# ICAN-7006-MIC.net
KiCad netlist of a schematic drawn in Altium Designer
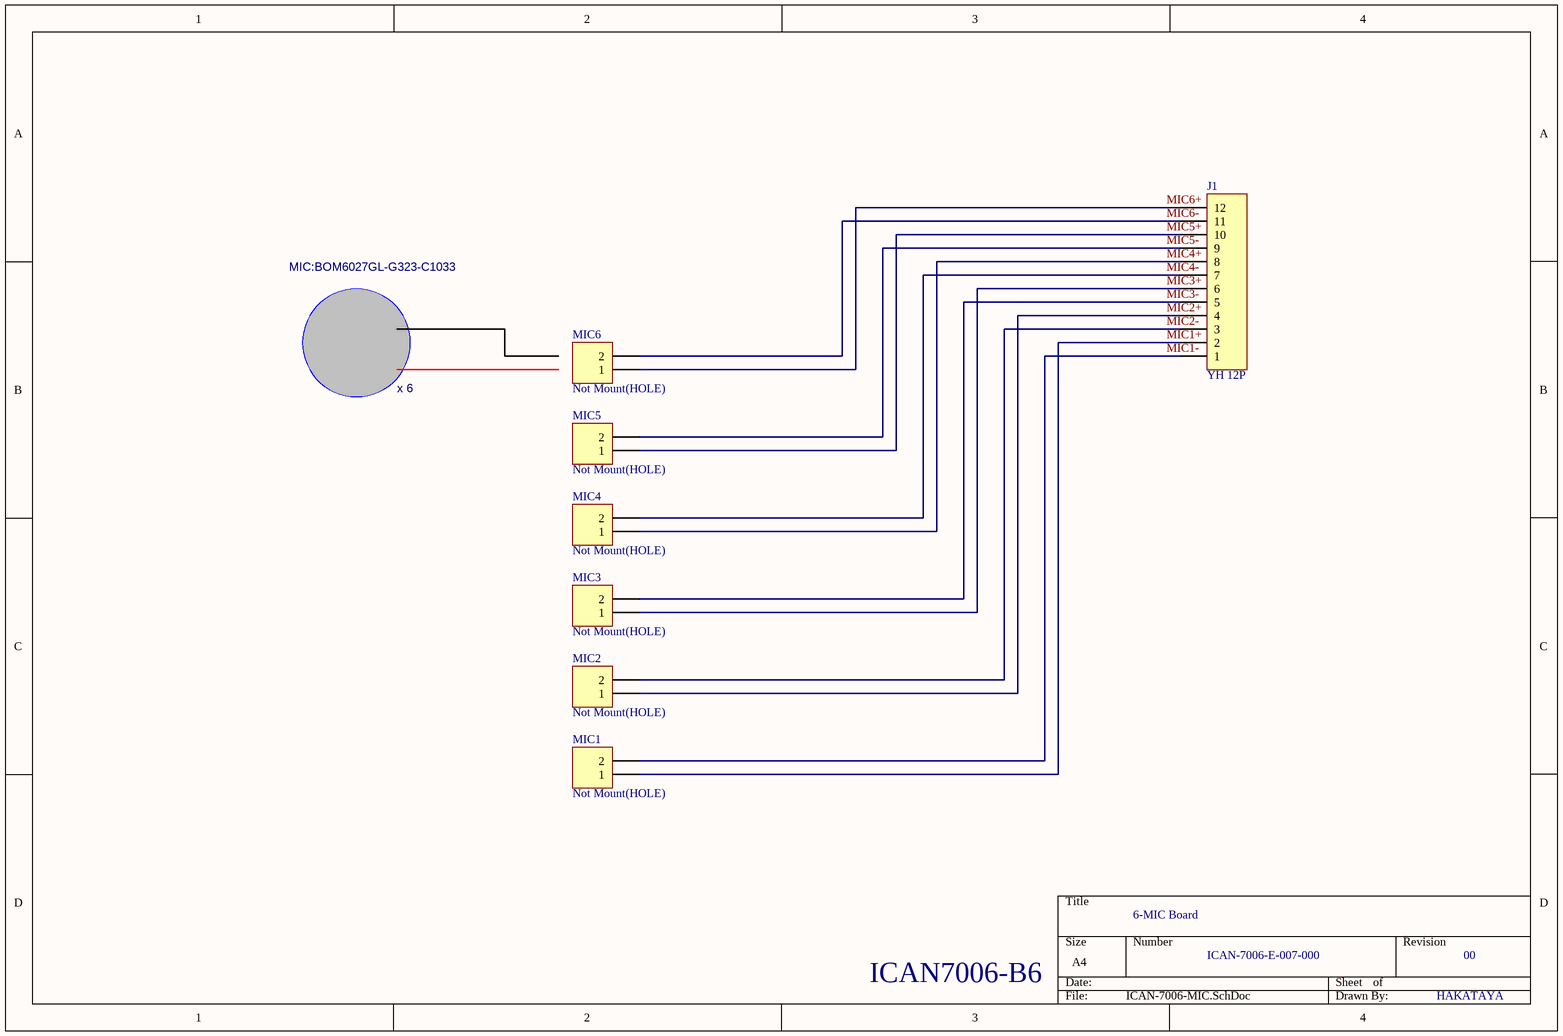
[diagram p0: ICAN-7006-MIC.SchDoc]

(export (version "E")
  (design (tool "Eeschema 10.0.6"))
  (components
    (comp (ref "J1")
      (value "YH 12P")
      (footprint "Miscellaneous Connectors:HDR2X6")
      (description "Header, 12-Pin")
      (fields (field (name "PUBLISHER") "Altium Limited"))
      (libsource (lib "Miscellaneous Connectors") (part "Header 12"))
    )
    (comp (ref "MIC1")
      (value "Not Mount(HOLE)")
      (footprint "Miscellaneous Connectors:MHDR1X2")
      (description "Header, 2-Pin")
      (fields (field (name "PUBLISHER") "Altium Limited"))
      (libsource (lib "Miscellaneous Connectors") (part "Header 2"))
    )
    (comp (ref "MIC2")
      (value "Not Mount(HOLE)")
      (footprint "Miscellaneous Connectors:MHDR1X2")
      (description "Header, 2-Pin")
      (fields (field (name "PUBLISHER") "Altium Limited"))
      (libsource (lib "Miscellaneous Connectors") (part "Header 2"))
    )
    (comp (ref "MIC3")
      (value "Not Mount(HOLE)")
      (footprint "Miscellaneous Connectors:MHDR1X2")
      (description "Header, 2-Pin")
      (fields (field (name "PUBLISHER") "Altium Limited"))
      (libsource (lib "Miscellaneous Connectors") (part "Header 2"))
    )
    (comp (ref "MIC4")
      (value "Not Mount(HOLE)")
      (footprint "Miscellaneous Connectors:MHDR1X2")
      (description "Header, 2-Pin")
      (fields (field (name "PUBLISHER") "Altium Limited"))
      (libsource (lib "Miscellaneous Connectors") (part "Header 2"))
    )
    (comp (ref "MIC5")
      (value "Not Mount(HOLE)")
      (footprint "Miscellaneous Connectors:MHDR1X2")
      (description "Header, 2-Pin")
      (fields (field (name "PUBLISHER") "Altium Limited"))
      (libsource (lib "Miscellaneous Connectors") (part "Header 2"))
    )
    (comp (ref "MIC6")
      (value "Not Mount(HOLE)")
      (footprint "Miscellaneous Connectors:MHDR1X2")
      (description "Header, 2-Pin")
      (fields (field (name "PUBLISHER") "Altium Limited"))
      (libsource (lib "Miscellaneous Connectors") (part "Header 2"))
    )
  )
  (nets
    (net (code "1") (name "/MIC1+") (class "Default")
      (node (ref "J1") (pin "2") (pinfunction "2_2") (pintype "passive"))
      (node (ref "MIC1") (pin "1") (pinfunction "1_1") (pintype "passive"))
    )
    (net (code "2") (name "/MIC1-") (class "Default")
      (node (ref "J1") (pin "1") (pinfunction "1_1") (pintype "passive"))
      (node (ref "MIC1") (pin "2") (pinfunction "2_2") (pintype "passive"))
    )
    (net (code "3") (name "/MIC2+") (class "Default")
      (node (ref "J1") (pin "4") (pinfunction "4_4") (pintype "passive"))
      (node (ref "MIC2") (pin "1") (pinfunction "1_1") (pintype "passive"))
    )
    (net (code "4") (name "/MIC2-") (class "Default")
      (node (ref "J1") (pin "3") (pinfunction "3_3") (pintype "passive"))
      (node (ref "MIC2") (pin "2") (pinfunction "2_2") (pintype "passive"))
    )
    (net (code "5") (name "/MIC3+") (class "Default")
      (node (ref "J1") (pin "6") (pinfunction "6_6") (pintype "passive"))
      (node (ref "MIC3") (pin "1") (pinfunction "1_1") (pintype "passive"))
    )
    (net (code "6") (name "/MIC3-") (class "Default")
      (node (ref "J1") (pin "5") (pinfunction "5_5") (pintype "passive"))
      (node (ref "MIC3") (pin "2") (pinfunction "2_2") (pintype "passive"))
    )
    (net (code "7") (name "/MIC4+") (class "Default")
      (node (ref "J1") (pin "8") (pinfunction "8_8") (pintype "passive"))
      (node (ref "MIC4") (pin "1") (pinfunction "1_1") (pintype "passive"))
    )
    (net (code "8") (name "/MIC4-") (class "Default")
      (node (ref "J1") (pin "7") (pinfunction "7_7") (pintype "passive"))
      (node (ref "MIC4") (pin "2") (pinfunction "2_2") (pintype "passive"))
    )
    (net (code "9") (name "/MIC5+") (class "Default")
      (node (ref "J1") (pin "10") (pinfunction "10_10") (pintype "passive"))
      (node (ref "MIC5") (pin "1") (pinfunction "1_1") (pintype "passive"))
    )
    (net (code "10") (name "/MIC5-") (class "Default")
      (node (ref "J1") (pin "9") (pinfunction "9_9") (pintype "passive"))
      (node (ref "MIC5") (pin "2") (pinfunction "2_2") (pintype "passive"))
    )
    (net (code "11") (name "/MIC6+") (class "Default")
      (node (ref "J1") (pin "12") (pinfunction "12_12") (pintype "passive"))
      (node (ref "MIC6") (pin "1") (pinfunction "1_1") (pintype "passive"))
    )
    (net (code "12") (name "/MIC6-") (class "Default")
      (node (ref "J1") (pin "11") (pinfunction "11_11") (pintype "passive"))
      (node (ref "MIC6") (pin "2") (pinfunction "2_2") (pintype "passive"))
    )
  )
)
